# SCH_RPi5-GPIO-Breakout-Board-_AI-Capsule.net
KiCad netlist of a schematic drawn in EasyEDA
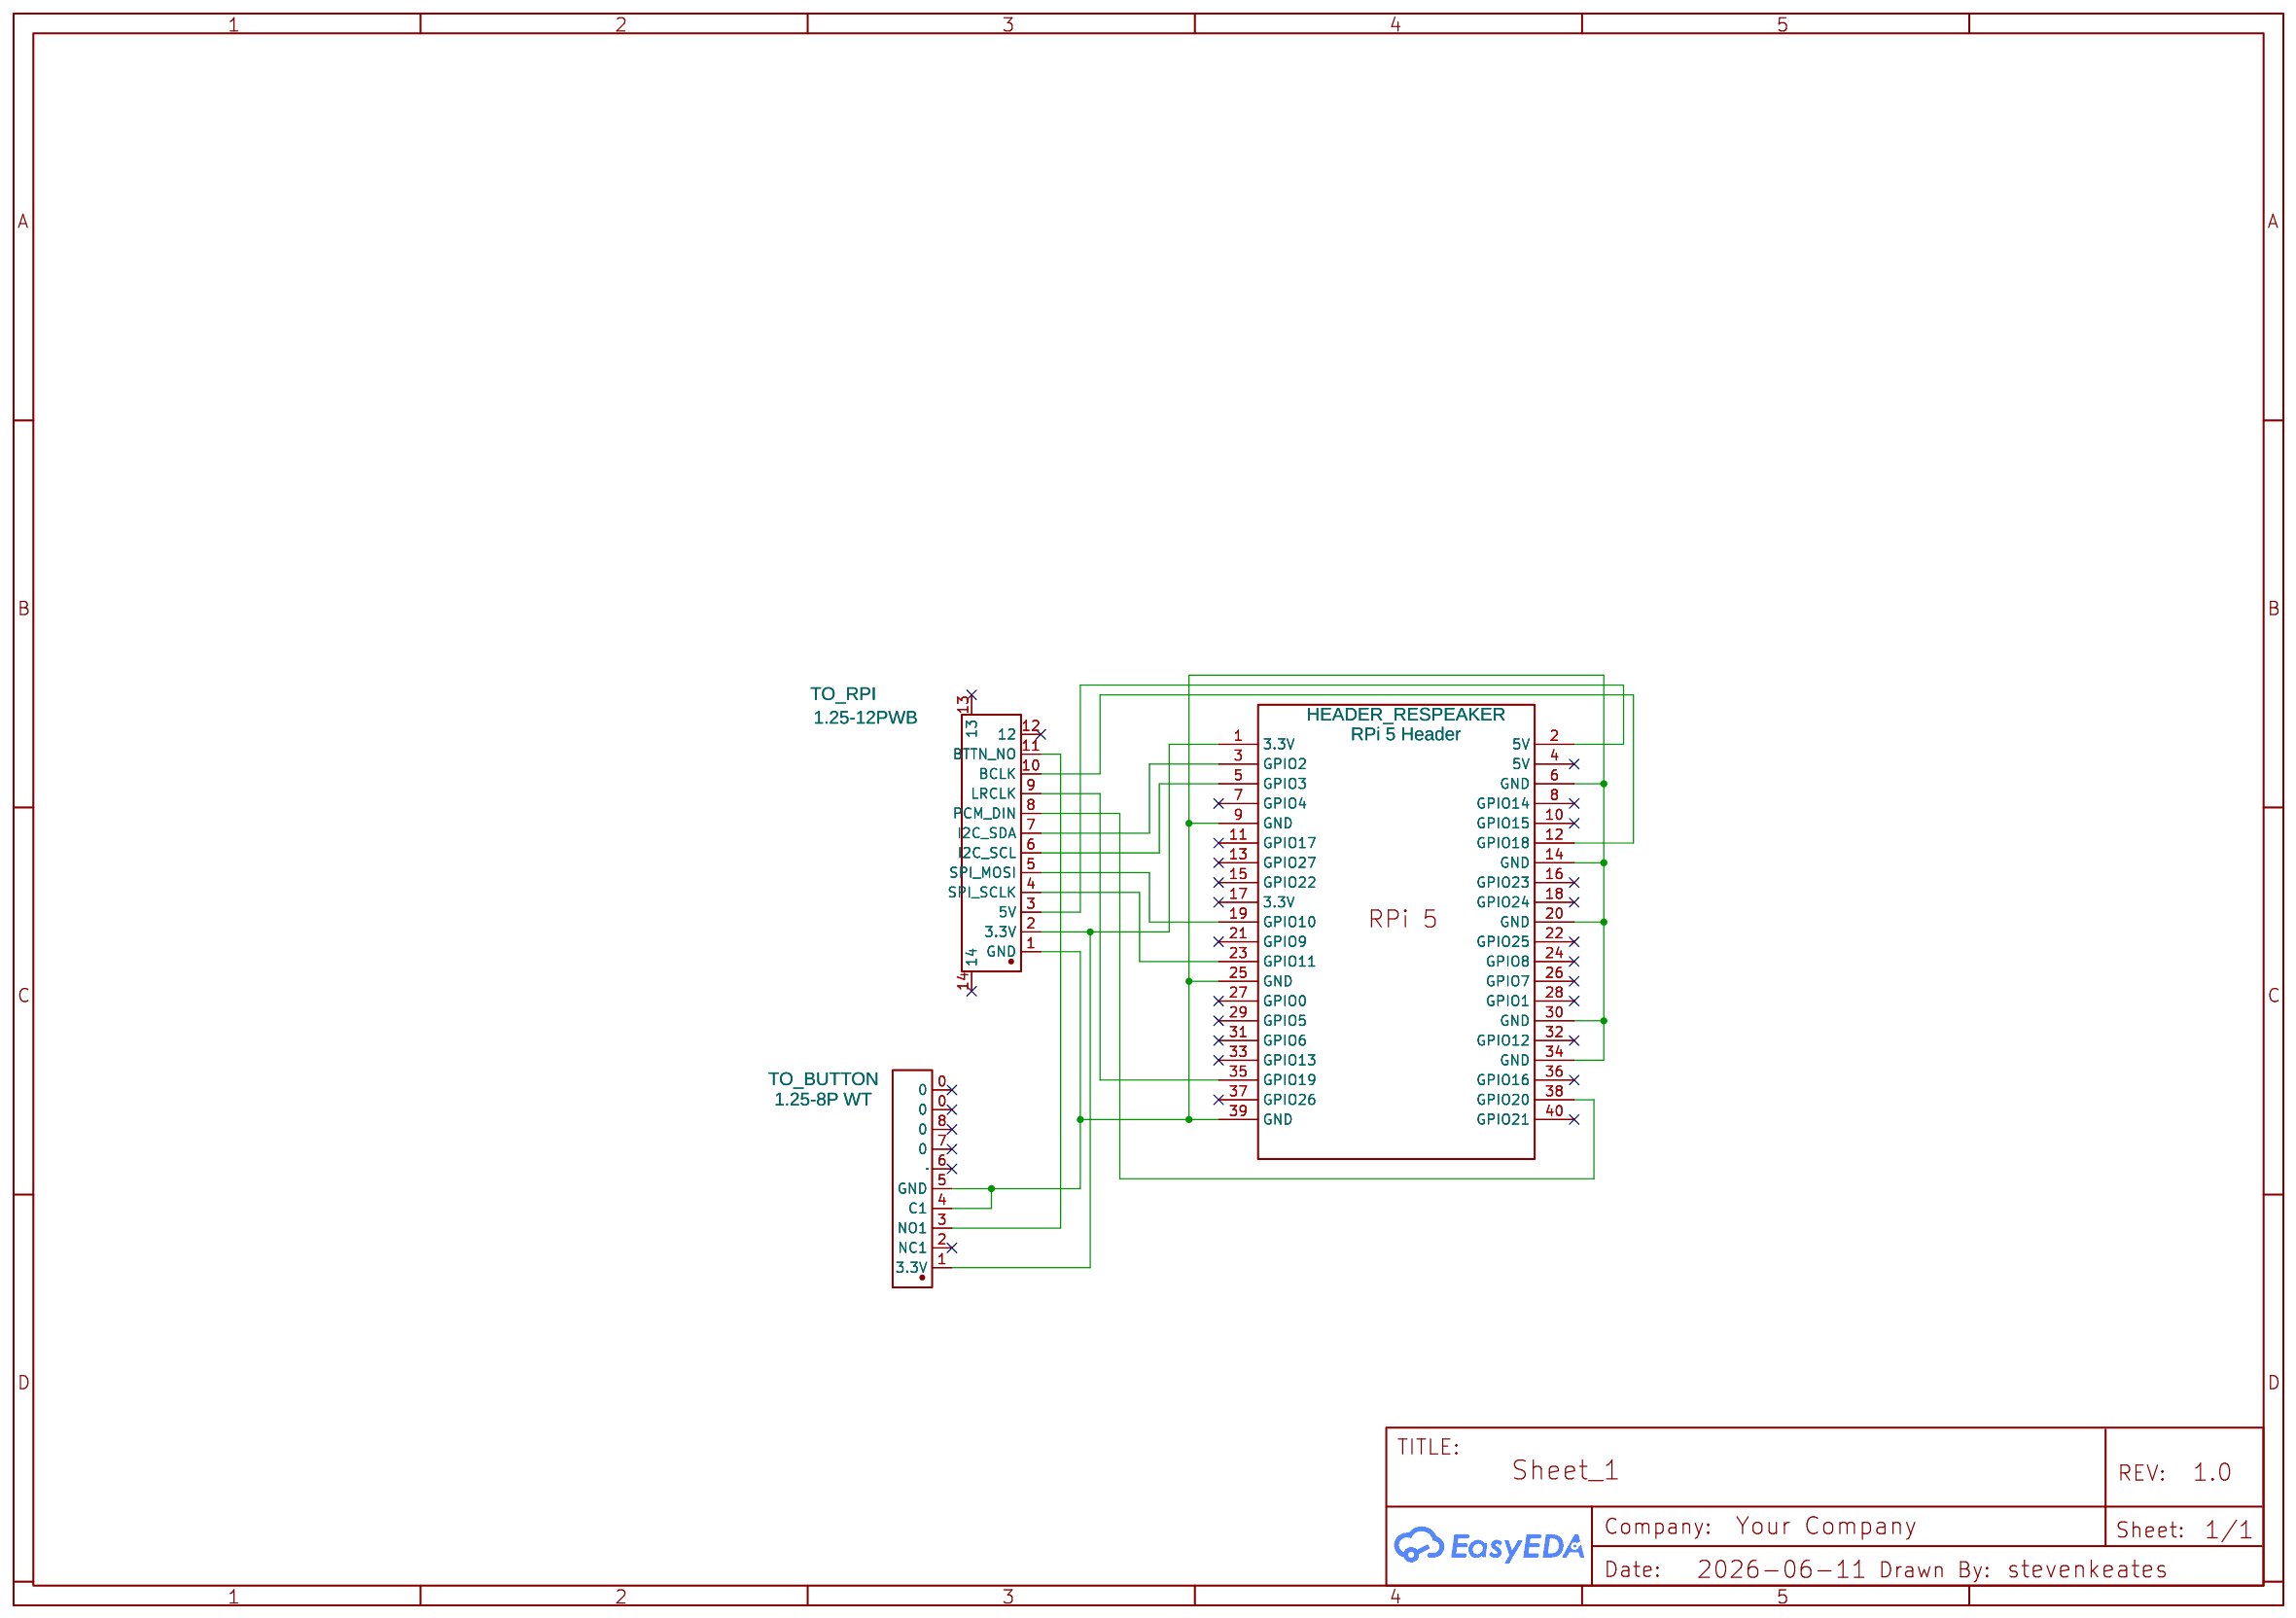
[diagram p0: SCH_Breakout Board (ReSpeaker)]
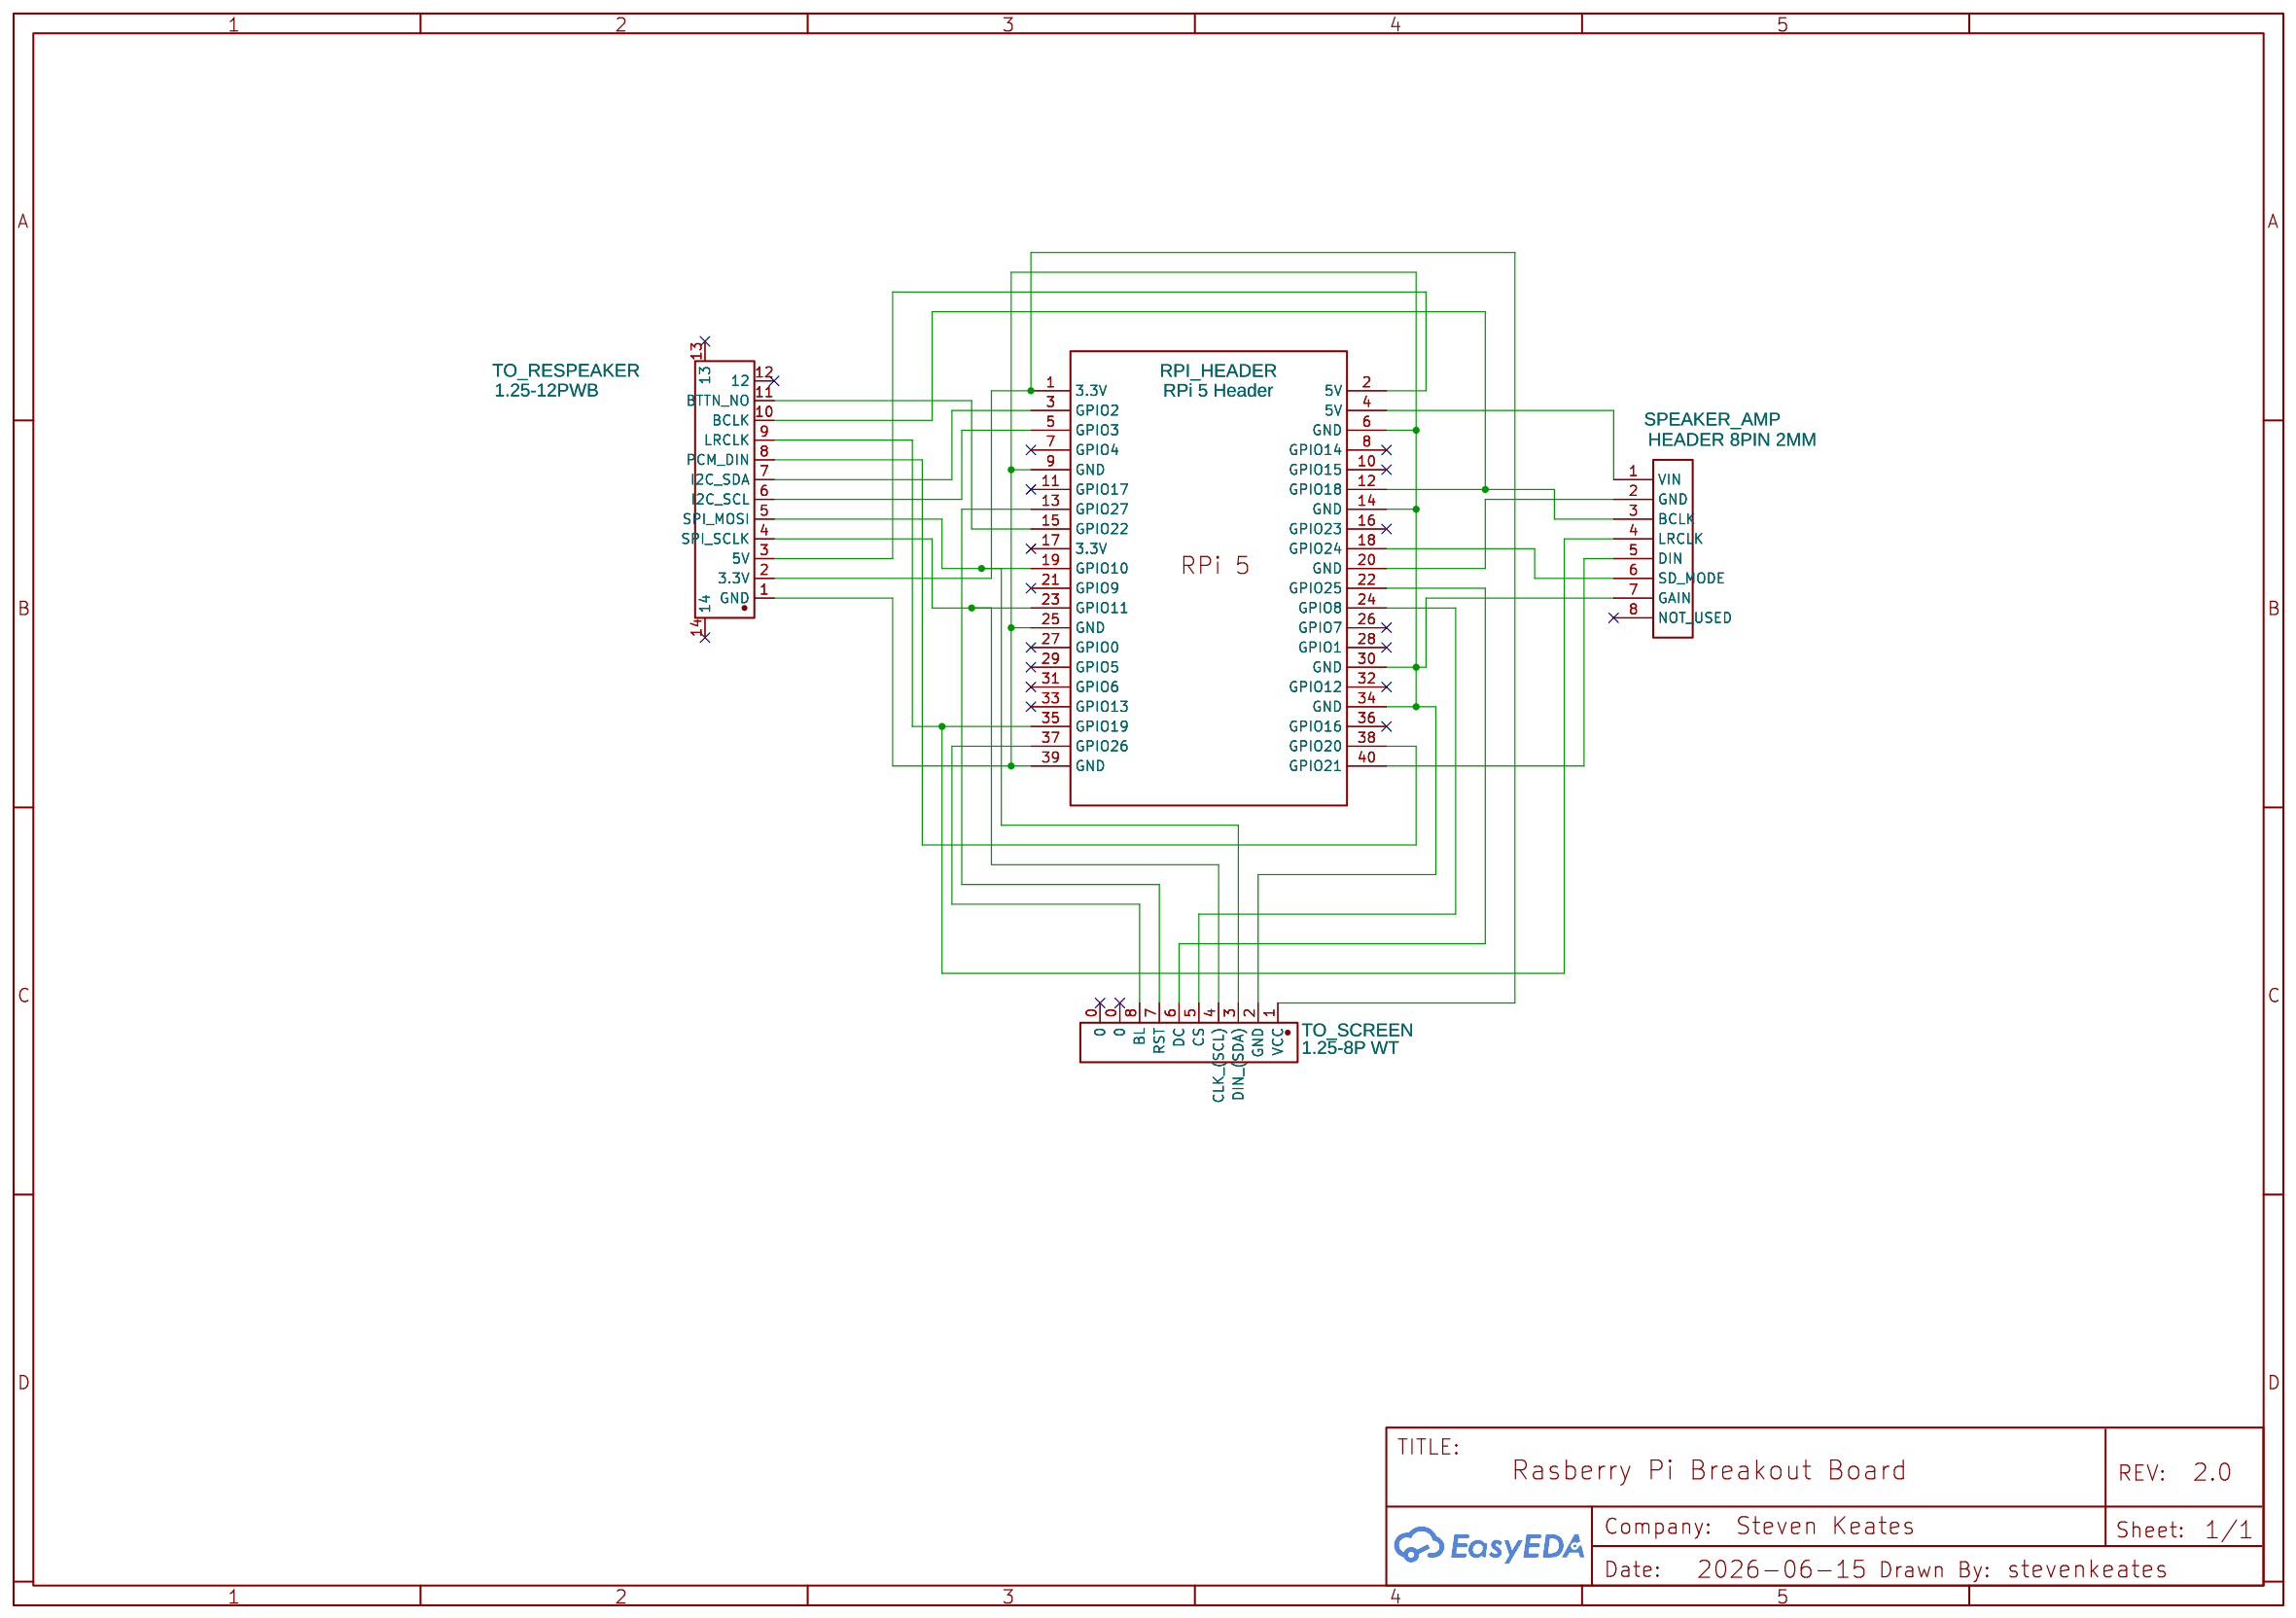
[diagram p1: SCH_Breakout Board (RPi 5)]

(export (version "E")
  (design (tool "Eeschema 10.0.6"))
  (components
    (comp (ref "HEADER_RESPEAKER")
      (value "RPi 5 Header")
      (fields (field (name "Manufacturer") "Raspberry Pi 5 4GB"))
      (libsource (lib "") (part "Raspberry Pi 5"))
    )
    (comp (ref "TO_BUTTON")
      (value "1.25-8P WT")
      (fields (field (name "Manufacturer") "SHOU HAN(首韩)"))
      (libsource (lib "") (part "1.25-8P WT"))
    )
    (comp (ref "TO_RPI")
      (value "1.25-12PWB")
      (fields (field (name "Manufacturer") "DEALON(德艺隆)"))
      (libsource (lib "") (part "1.25-12PWB"))
    )
    (comp (ref "RPI_HEADER")
      (value "RPi 5 Header")
      (fields (field (name "Manufacturer") "Raspberry Pi 5 4GB"))
      (libsource (lib "") (part "Raspberry Pi 5"))
    )
    (comp (ref "SPEAKER_AMP") (value "HEADER 8PIN 2MM") (libsource (lib "") (part "HEADER 8PIN 2MM")))
    (comp (ref "TO_RESPEAKER")
      (value "1.25-12PWB")
      (fields (field (name "Manufacturer") "DEALON(德艺隆)"))
      (libsource (lib "") (part "1.25-12PWB"))
    )
    (comp (ref "TO_SCREEN")
      (value "1.25-8P WT")
      (fields (field (name "Manufacturer") "SHOU HAN(首韩)"))
      (libsource (lib "") (part "1.25-8P WT"))
    )
  )
  (nets
    (net (code "1") (name "Net-(HEADER_RESPEAKER-GPIO2)") (class "Default")
      (node (ref "HEADER_RESPEAKER") (pin "3") (pinfunction "GPIO2_3") (pintype "unspecified"))
      (node (ref "TO_RPI") (pin "7") (pinfunction "I2C_SDA_7") (pintype "unspecified"))
    )
    (net (code "2") (name "Net-(HEADER_RESPEAKER-GPIO3)") (class "Default")
      (node (ref "HEADER_RESPEAKER") (pin "5") (pinfunction "GPIO3_5") (pintype "unspecified"))
      (node (ref "TO_RPI") (pin "6") (pinfunction "I2C_SCL_6") (pintype "unspecified"))
    )
    (net (code "3") (name "Net-(HEADER_RESPEAKER-GPIO10)") (class "Default")
      (node (ref "HEADER_RESPEAKER") (pin "19") (pinfunction "GPIO10_19") (pintype "unspecified"))
      (node (ref "TO_RPI") (pin "5") (pinfunction "SPI_MOSI_5") (pintype "unspecified"))
    )
    (net (code "4") (name "Net-(HEADER_RESPEAKER-GPIO11)") (class "Default")
      (node (ref "HEADER_RESPEAKER") (pin "23") (pinfunction "GPIO11_23") (pintype "unspecified"))
      (node (ref "TO_RPI") (pin "4") (pinfunction "SPI_SCLK_4") (pintype "unspecified"))
    )
    (net (code "5") (name "Net-(HEADER_RESPEAKER-GPIO18)") (class "Default")
      (node (ref "HEADER_RESPEAKER") (pin "12") (pinfunction "GPIO18_12") (pintype "unspecified"))
      (node (ref "TO_RPI") (pin "10") (pinfunction "BCLK_10") (pintype "unspecified"))
    )
    (net (code "6") (name "Net-(HEADER_RESPEAKER-GPIO19)") (class "Default")
      (node (ref "HEADER_RESPEAKER") (pin "35") (pinfunction "GPIO19_35") (pintype "unspecified"))
      (node (ref "TO_RPI") (pin "9") (pinfunction "LRCLK_9") (pintype "unspecified"))
    )
    (net (code "7") (name "Net-(HEADER_RESPEAKER-GPIO20)") (class "Default")
      (node (ref "HEADER_RESPEAKER") (pin "38") (pinfunction "GPIO20_38") (pintype "unspecified"))
      (node (ref "TO_RPI") (pin "8") (pinfunction "PCM_DIN_8") (pintype "unspecified"))
    )
    (net (code "8") (name "Net-(RPI_HEADER-GPIO2)") (class "Default")
      (node (ref "RPI_HEADER") (pin "3") (pinfunction "GPIO2_3") (pintype "unspecified"))
      (node (ref "TO_RESPEAKER") (pin "7") (pinfunction "I2C_SDA_7") (pintype "unspecified"))
    )
    (net (code "9") (name "Net-(RPI_HEADER-GPIO3)") (class "Default")
      (node (ref "RPI_HEADER") (pin "5") (pinfunction "GPIO3_5") (pintype "unspecified"))
      (node (ref "TO_RESPEAKER") (pin "6") (pinfunction "I2C_SCL_6") (pintype "unspecified"))
    )
    (net (code "10") (name "Net-(RPI_HEADER-GPIO8)") (class "Default")
      (node (ref "RPI_HEADER") (pin "24") (pinfunction "GPIO8_24") (pintype "unspecified"))
      (node (ref "TO_SCREEN") (pin "5") (pinfunction "CS_5") (pintype "unspecified"))
    )
    (net (code "11") (name "Net-(RPI_HEADER-GPIO10)") (class "Default")
      (node (ref "RPI_HEADER") (pin "19") (pinfunction "GPIO10_19") (pintype "unspecified"))
      (node (ref "TO_RESPEAKER") (pin "5") (pinfunction "SPI_MOSI_5") (pintype "unspecified"))
      (node (ref "TO_SCREEN") (pin "3") (pinfunction "DIN_(SDA)_3") (pintype "unspecified"))
    )
    (net (code "12") (name "Net-(RPI_HEADER-GPIO11)") (class "Default")
      (node (ref "RPI_HEADER") (pin "23") (pinfunction "GPIO11_23") (pintype "unspecified"))
      (node (ref "TO_RESPEAKER") (pin "4") (pinfunction "SPI_SCLK_4") (pintype "unspecified"))
      (node (ref "TO_SCREEN") (pin "4") (pinfunction "CLK_(SCL)_4") (pintype "unspecified"))
    )
    (net (code "13") (name "Net-(RPI_HEADER-GPIO18)") (class "Default")
      (node (ref "RPI_HEADER") (pin "12") (pinfunction "GPIO18_12") (pintype "unspecified"))
      (node (ref "SPEAKER_AMP") (pin "3") (pinfunction "BCLK_3") (pintype "unspecified"))
      (node (ref "TO_RESPEAKER") (pin "10") (pinfunction "BCLK_10") (pintype "unspecified"))
    )
    (net (code "14") (name "Net-(RPI_HEADER-GPIO19)") (class "Default")
      (node (ref "RPI_HEADER") (pin "35") (pinfunction "GPIO19_35") (pintype "unspecified"))
      (node (ref "SPEAKER_AMP") (pin "4") (pinfunction "LRCLK_4") (pintype "unspecified"))
      (node (ref "TO_RESPEAKER") (pin "9") (pinfunction "LRCLK_9") (pintype "unspecified"))
    )
    (net (code "15") (name "Net-(RPI_HEADER-GPIO20)") (class "Default")
      (node (ref "RPI_HEADER") (pin "38") (pinfunction "GPIO20_38") (pintype "unspecified"))
      (node (ref "TO_RESPEAKER") (pin "8") (pinfunction "PCM_DIN_8") (pintype "unspecified"))
    )
    (net (code "16") (name "Net-(RPI_HEADER-GPIO21)") (class "Default")
      (node (ref "RPI_HEADER") (pin "40") (pinfunction "GPIO21_40") (pintype "unspecified"))
      (node (ref "SPEAKER_AMP") (pin "5") (pinfunction "DIN_5") (pintype "unspecified"))
    )
    (net (code "17") (name "Net-(RPI_HEADER-GPIO22)") (class "Default")
      (node (ref "RPI_HEADER") (pin "15") (pinfunction "GPIO22_15") (pintype "unspecified"))
      (node (ref "TO_RESPEAKER") (pin "11") (pinfunction "BTTN_NO_11") (pintype "unspecified"))
    )
    (net (code "18") (name "Net-(RPI_HEADER-GPIO24)") (class "Default")
      (node (ref "RPI_HEADER") (pin "18") (pinfunction "GPIO24_18") (pintype "unspecified"))
      (node (ref "SPEAKER_AMP") (pin "6") (pinfunction "SD_MODE_6") (pintype "unspecified"))
    )
    (net (code "19") (name "Net-(RPI_HEADER-GPIO25)") (class "Default")
      (node (ref "RPI_HEADER") (pin "22") (pinfunction "GPIO25_22") (pintype "unspecified"))
      (node (ref "TO_SCREEN") (pin "6") (pinfunction "DC_6") (pintype "unspecified"))
    )
    (net (code "20") (name "Net-(RPI_HEADER-GPIO26)") (class "Default")
      (node (ref "RPI_HEADER") (pin "37") (pinfunction "GPIO26_37") (pintype "unspecified"))
      (node (ref "TO_SCREEN") (pin "8") (pinfunction "BL_8") (pintype "unspecified"))
    )
    (net (code "21") (name "Net-(RPI_HEADER-GPIO27)") (class "Default")
      (node (ref "RPI_HEADER") (pin "13") (pinfunction "GPIO27_13") (pintype "unspecified"))
      (node (ref "TO_SCREEN") (pin "7") (pinfunction "RST_7") (pintype "unspecified"))
    )
    (net (code "22") (name "Net-(SPEAKER_AMP-GAIN)") (class "Default")
      (node (ref "RPI_HEADER") (pin "14") (pinfunction "GND_14") (pintype "unspecified"))
      (node (ref "RPI_HEADER") (pin "25") (pinfunction "GND_25") (pintype "unspecified"))
      (node (ref "RPI_HEADER") (pin "30") (pinfunction "GND_30") (pintype "unspecified"))
      (node (ref "RPI_HEADER") (pin "34") (pinfunction "GND_34") (pintype "unspecified"))
      (node (ref "RPI_HEADER") (pin "39") (pinfunction "GND_39") (pintype "unspecified"))
      (node (ref "RPI_HEADER") (pin "6") (pinfunction "GND_6") (pintype "unspecified"))
      (node (ref "RPI_HEADER") (pin "9") (pinfunction "GND_9") (pintype "unspecified"))
      (node (ref "SPEAKER_AMP") (pin "7") (pinfunction "GAIN_7") (pintype "unspecified"))
      (node (ref "TO_RESPEAKER") (pin "1") (pinfunction "GND_1") (pintype "unspecified"))
      (node (ref "TO_SCREEN") (pin "2") (pinfunction "GND_2") (pintype "unspecified"))
    )
    (net (code "23") (name "Net-(SPEAKER_AMP-GND)") (class "Default")
      (node (ref "RPI_HEADER") (pin "20") (pinfunction "GND_20") (pintype "unspecified"))
      (node (ref "SPEAKER_AMP") (pin "2") (pinfunction "GND_2") (pintype "unspecified"))
    )
    (net (code "24") (name "Net-(SPEAKER_AMP-VIN)") (class "Default")
      (node (ref "RPI_HEADER") (pin "4") (pinfunction "5V_4") (pintype "unspecified"))
      (node (ref "SPEAKER_AMP") (pin "1") (pinfunction "VIN_1") (pintype "unspecified"))
    )
    (net (code "25") (name "Net-(TO_BUTTON-3.3V)") (class "Default")
      (node (ref "HEADER_RESPEAKER") (pin "1") (pinfunction "3.3V_1") (pintype "unspecified"))
      (node (ref "TO_BUTTON") (pin "1") (pinfunction "3.3V_1") (pintype "unspecified"))
      (node (ref "TO_RPI") (pin "2") (pinfunction "3.3V_2") (pintype "unspecified"))
    )
    (net (code "26") (name "Net-(TO_BUTTON-C1)") (class "Default")
      (node (ref "HEADER_RESPEAKER") (pin "14") (pinfunction "GND_14") (pintype "unspecified"))
      (node (ref "HEADER_RESPEAKER") (pin "20") (pinfunction "GND_20") (pintype "unspecified"))
      (node (ref "HEADER_RESPEAKER") (pin "25") (pinfunction "GND_25") (pintype "unspecified"))
      (node (ref "HEADER_RESPEAKER") (pin "30") (pinfunction "GND_30") (pintype "unspecified"))
      (node (ref "HEADER_RESPEAKER") (pin "34") (pinfunction "GND_34") (pintype "unspecified"))
      (node (ref "HEADER_RESPEAKER") (pin "39") (pinfunction "GND_39") (pintype "unspecified"))
      (node (ref "HEADER_RESPEAKER") (pin "6") (pinfunction "GND_6") (pintype "unspecified"))
      (node (ref "HEADER_RESPEAKER") (pin "9") (pinfunction "GND_9") (pintype "unspecified"))
      (node (ref "TO_BUTTON") (pin "4") (pinfunction "C1_4") (pintype "unspecified"))
      (node (ref "TO_BUTTON") (pin "5") (pinfunction "GND_5") (pintype "unspecified"))
      (node (ref "TO_RPI") (pin "1") (pinfunction "GND_1") (pintype "unspecified"))
    )
    (net (code "27") (name "Net-(TO_BUTTON-NO1)") (class "Default")
      (node (ref "TO_BUTTON") (pin "3") (pinfunction "NO1_3") (pintype "unspecified"))
      (node (ref "TO_RPI") (pin "11") (pinfunction "BTTN_NO_11") (pintype "unspecified"))
    )
    (net (code "28") (name "Net-(TO_RESPEAKER-3.3V)") (class "Default")
      (node (ref "RPI_HEADER") (pin "1") (pinfunction "3.3V_1") (pintype "unspecified"))
      (node (ref "TO_RESPEAKER") (pin "2") (pinfunction "3.3V_2") (pintype "unspecified"))
      (node (ref "TO_SCREEN") (pin "1") (pinfunction "VCC_1") (pintype "unspecified"))
    )
    (net (code "29") (name "Net-(TO_RESPEAKER-5V)") (class "Default")
      (node (ref "RPI_HEADER") (pin "2") (pinfunction "5V_2") (pintype "unspecified"))
      (node (ref "TO_RESPEAKER") (pin "3") (pinfunction "5V_3") (pintype "unspecified"))
    )
    (net (code "30") (name "Net-(TO_RPI-5V)") (class "Default")
      (node (ref "HEADER_RESPEAKER") (pin "2") (pinfunction "5V_2") (pintype "unspecified"))
      (node (ref "TO_RPI") (pin "3") (pinfunction "5V_3") (pintype "unspecified"))
    )
    (net (code "31") (name "unconnected-(HEADER_RESPEAKER-3.3V-Pad17)") (class "Default")
      (node (ref "HEADER_RESPEAKER") (pin "17") (pinfunction "3.3V_17") (pintype "unspecified+no_connect"))
    )
    (net (code "32") (name "unconnected-(HEADER_RESPEAKER-5V-Pad4)") (class "Default")
      (node (ref "HEADER_RESPEAKER") (pin "4") (pinfunction "5V_4") (pintype "unspecified+no_connect"))
    )
    (net (code "33") (name "unconnected-(HEADER_RESPEAKER-GPIO0-Pad27)") (class "Default")
      (node (ref "HEADER_RESPEAKER") (pin "27") (pinfunction "GPIO0_27") (pintype "unspecified+no_connect"))
    )
    (net (code "34") (name "unconnected-(HEADER_RESPEAKER-GPIO1-Pad28)") (class "Default")
      (node (ref "HEADER_RESPEAKER") (pin "28") (pinfunction "GPIO1_28") (pintype "unspecified+no_connect"))
    )
    (net (code "35") (name "unconnected-(HEADER_RESPEAKER-GPIO4-Pad7)") (class "Default")
      (node (ref "HEADER_RESPEAKER") (pin "7") (pinfunction "GPIO4_7") (pintype "unspecified+no_connect"))
    )
    (net (code "36") (name "unconnected-(HEADER_RESPEAKER-GPIO5-Pad29)") (class "Default")
      (node (ref "HEADER_RESPEAKER") (pin "29") (pinfunction "GPIO5_29") (pintype "unspecified+no_connect"))
    )
    (net (code "37") (name "unconnected-(HEADER_RESPEAKER-GPIO6-Pad31)") (class "Default")
      (node (ref "HEADER_RESPEAKER") (pin "31") (pinfunction "GPIO6_31") (pintype "unspecified+no_connect"))
    )
    (net (code "38") (name "unconnected-(HEADER_RESPEAKER-GPIO7-Pad26)") (class "Default")
      (node (ref "HEADER_RESPEAKER") (pin "26") (pinfunction "GPIO7_26") (pintype "unspecified+no_connect"))
    )
    (net (code "39") (name "unconnected-(HEADER_RESPEAKER-GPIO8-Pad24)") (class "Default")
      (node (ref "HEADER_RESPEAKER") (pin "24") (pinfunction "GPIO8_24") (pintype "unspecified+no_connect"))
    )
    (net (code "40") (name "unconnected-(HEADER_RESPEAKER-GPIO9-Pad21)") (class "Default")
      (node (ref "HEADER_RESPEAKER") (pin "21") (pinfunction "GPIO9_21") (pintype "unspecified+no_connect"))
    )
    (net (code "41") (name "unconnected-(HEADER_RESPEAKER-GPIO12-Pad32)") (class "Default")
      (node (ref "HEADER_RESPEAKER") (pin "32") (pinfunction "GPIO12_32") (pintype "unspecified+no_connect"))
    )
    (net (code "42") (name "unconnected-(HEADER_RESPEAKER-GPIO13-Pad33)") (class "Default")
      (node (ref "HEADER_RESPEAKER") (pin "33") (pinfunction "GPIO13_33") (pintype "unspecified+no_connect"))
    )
    (net (code "43") (name "unconnected-(HEADER_RESPEAKER-GPIO14-Pad8)") (class "Default")
      (node (ref "HEADER_RESPEAKER") (pin "8") (pinfunction "GPIO14_8") (pintype "unspecified+no_connect"))
    )
    (net (code "44") (name "unconnected-(HEADER_RESPEAKER-GPIO15-Pad10)") (class "Default")
      (node (ref "HEADER_RESPEAKER") (pin "10") (pinfunction "GPIO15_10") (pintype "unspecified+no_connect"))
    )
    (net (code "45") (name "unconnected-(HEADER_RESPEAKER-GPIO16-Pad36)") (class "Default")
      (node (ref "HEADER_RESPEAKER") (pin "36") (pinfunction "GPIO16_36") (pintype "unspecified+no_connect"))
    )
    (net (code "46") (name "unconnected-(HEADER_RESPEAKER-GPIO17-Pad11)") (class "Default")
      (node (ref "HEADER_RESPEAKER") (pin "11") (pinfunction "GPIO17_11") (pintype "unspecified+no_connect"))
    )
    (net (code "47") (name "unconnected-(HEADER_RESPEAKER-GPIO21-Pad40)") (class "Default")
      (node (ref "HEADER_RESPEAKER") (pin "40") (pinfunction "GPIO21_40") (pintype "unspecified+no_connect"))
    )
    (net (code "48") (name "unconnected-(HEADER_RESPEAKER-GPIO22-Pad15)") (class "Default")
      (node (ref "HEADER_RESPEAKER") (pin "15") (pinfunction "GPIO22_15") (pintype "unspecified+no_connect"))
    )
    (net (code "49") (name "unconnected-(HEADER_RESPEAKER-GPIO23-Pad16)") (class "Default")
      (node (ref "HEADER_RESPEAKER") (pin "16") (pinfunction "GPIO23_16") (pintype "unspecified+no_connect"))
    )
    (net (code "50") (name "unconnected-(HEADER_RESPEAKER-GPIO24-Pad18)") (class "Default")
      (node (ref "HEADER_RESPEAKER") (pin "18") (pinfunction "GPIO24_18") (pintype "unspecified+no_connect"))
    )
    (net (code "51") (name "unconnected-(HEADER_RESPEAKER-GPIO25-Pad22)") (class "Default")
      (node (ref "HEADER_RESPEAKER") (pin "22") (pinfunction "GPIO25_22") (pintype "unspecified+no_connect"))
    )
    (net (code "52") (name "unconnected-(HEADER_RESPEAKER-GPIO26-Pad37)") (class "Default")
      (node (ref "HEADER_RESPEAKER") (pin "37") (pinfunction "GPIO26_37") (pintype "unspecified+no_connect"))
    )
    (net (code "53") (name "unconnected-(HEADER_RESPEAKER-GPIO27-Pad13)") (class "Default")
      (node (ref "HEADER_RESPEAKER") (pin "13") (pinfunction "GPIO27_13") (pintype "unspecified+no_connect"))
    )
    (net (code "54") (name "unconnected-(RPI_HEADER-3.3V-Pad17)") (class "Default")
      (node (ref "RPI_HEADER") (pin "17") (pinfunction "3.3V_17") (pintype "unspecified+no_connect"))
    )
    (net (code "55") (name "unconnected-(RPI_HEADER-GPIO0-Pad27)") (class "Default")
      (node (ref "RPI_HEADER") (pin "27") (pinfunction "GPIO0_27") (pintype "unspecified+no_connect"))
    )
    (net (code "56") (name "unconnected-(RPI_HEADER-GPIO1-Pad28)") (class "Default")
      (node (ref "RPI_HEADER") (pin "28") (pinfunction "GPIO1_28") (pintype "unspecified+no_connect"))
    )
    (net (code "57") (name "unconnected-(RPI_HEADER-GPIO4-Pad7)") (class "Default")
      (node (ref "RPI_HEADER") (pin "7") (pinfunction "GPIO4_7") (pintype "unspecified+no_connect"))
    )
    (net (code "58") (name "unconnected-(RPI_HEADER-GPIO5-Pad29)") (class "Default")
      (node (ref "RPI_HEADER") (pin "29") (pinfunction "GPIO5_29") (pintype "unspecified+no_connect"))
    )
    (net (code "59") (name "unconnected-(RPI_HEADER-GPIO6-Pad31)") (class "Default")
      (node (ref "RPI_HEADER") (pin "31") (pinfunction "GPIO6_31") (pintype "unspecified+no_connect"))
    )
    (net (code "60") (name "unconnected-(RPI_HEADER-GPIO7-Pad26)") (class "Default")
      (node (ref "RPI_HEADER") (pin "26") (pinfunction "GPIO7_26") (pintype "unspecified+no_connect"))
    )
    (net (code "61") (name "unconnected-(RPI_HEADER-GPIO9-Pad21)") (class "Default")
      (node (ref "RPI_HEADER") (pin "21") (pinfunction "GPIO9_21") (pintype "unspecified+no_connect"))
    )
    (net (code "62") (name "unconnected-(RPI_HEADER-GPIO12-Pad32)") (class "Default")
      (node (ref "RPI_HEADER") (pin "32") (pinfunction "GPIO12_32") (pintype "unspecified+no_connect"))
    )
    (net (code "63") (name "unconnected-(RPI_HEADER-GPIO13-Pad33)") (class "Default")
      (node (ref "RPI_HEADER") (pin "33") (pinfunction "GPIO13_33") (pintype "unspecified+no_connect"))
    )
    (net (code "64") (name "unconnected-(RPI_HEADER-GPIO14-Pad8)") (class "Default")
      (node (ref "RPI_HEADER") (pin "8") (pinfunction "GPIO14_8") (pintype "unspecified+no_connect"))
    )
    (net (code "65") (name "unconnected-(RPI_HEADER-GPIO15-Pad10)") (class "Default")
      (node (ref "RPI_HEADER") (pin "10") (pinfunction "GPIO15_10") (pintype "unspecified+no_connect"))
    )
    (net (code "66") (name "unconnected-(RPI_HEADER-GPIO16-Pad36)") (class "Default")
      (node (ref "RPI_HEADER") (pin "36") (pinfunction "GPIO16_36") (pintype "unspecified+no_connect"))
    )
    (net (code "67") (name "unconnected-(RPI_HEADER-GPIO17-Pad11)") (class "Default")
      (node (ref "RPI_HEADER") (pin "11") (pinfunction "GPIO17_11") (pintype "unspecified+no_connect"))
    )
    (net (code "68") (name "unconnected-(RPI_HEADER-GPIO23-Pad16)") (class "Default")
      (node (ref "RPI_HEADER") (pin "16") (pinfunction "GPIO23_16") (pintype "unspecified+no_connect"))
    )
    (net (code "69") (name "unconnected-(SPEAKER_AMP-NOT_USED-Pad8)") (class "Default")
      (node (ref "SPEAKER_AMP") (pin "8") (pinfunction "NOT_USED_8") (pintype "unspecified+no_connect"))
    )
    (net (code "70") (name "unconnected-(TO_BUTTON-0-Pad7)") (class "Default")
      (node (ref "TO_BUTTON") (pin "7") (pinfunction "0_7") (pintype "unspecified+no_connect"))
    )
    (net (code "71") (name "unconnected-(TO_BUTTON-0-Pad8)") (class "Default")
      (node (ref "TO_BUTTON") (pin "8") (pinfunction "0_8") (pintype "unspecified+no_connect"))
    )
    (net (code "72") (name "unconnected-(TO_BUTTON-DC-Pad6)") (class "Default")
      (node (ref "TO_BUTTON") (pin "6") (pinfunction "DC_6") (pintype "unspecified+no_connect"))
    )
    (net (code "73") (name "unconnected-(TO_BUTTON-NC1-Pad2)") (class "Default")
      (node (ref "TO_BUTTON") (pin "2") (pinfunction "NC1_2") (pintype "unspecified+no_connect"))
    )
    (net (code "74") (name "unconnected-(TO_BUTTON-Pad0)") (class "Default")
      (node (ref "TO_BUTTON") (pin "0") (pinfunction "0_0") (pintype "unspecified+no_connect"))
    )
    (net (code "75") (name "unconnected-(TO_BUTTON-Pad0)_1") (class "Default")
      (node (ref "TO_BUTTON") (pin "0") (pinfunction "0_0") (pintype "unspecified+no_connect"))
    )
    (net (code "76") (name "unconnected-(TO_RESPEAKER-Pad12)") (class "Default")
      (node (ref "TO_RESPEAKER") (pin "12") (pinfunction "12_12") (pintype "unspecified+no_connect"))
    )
    (net (code "77") (name "unconnected-(TO_RESPEAKER-Pad13)") (class "Default")
      (node (ref "TO_RESPEAKER") (pin "13") (pinfunction "13_13") (pintype "unspecified+no_connect"))
    )
    (net (code "78") (name "unconnected-(TO_RESPEAKER-Pad14)") (class "Default")
      (node (ref "TO_RESPEAKER") (pin "14") (pinfunction "14_14") (pintype "unspecified+no_connect"))
    )
    (net (code "79") (name "unconnected-(TO_RPI-Pad12)") (class "Default")
      (node (ref "TO_RPI") (pin "12") (pinfunction "12_12") (pintype "unspecified+no_connect"))
    )
    (net (code "80") (name "unconnected-(TO_RPI-Pad13)") (class "Default")
      (node (ref "TO_RPI") (pin "13") (pinfunction "13_13") (pintype "unspecified+no_connect"))
    )
    (net (code "81") (name "unconnected-(TO_RPI-Pad14)") (class "Default")
      (node (ref "TO_RPI") (pin "14") (pinfunction "14_14") (pintype "unspecified+no_connect"))
    )
    (net (code "82") (name "unconnected-(TO_SCREEN-Pad0)") (class "Default")
      (node (ref "TO_SCREEN") (pin "0") (pinfunction "0_0") (pintype "unspecified+no_connect"))
    )
    (net (code "83") (name "unconnected-(TO_SCREEN-Pad0)_1") (class "Default")
      (node (ref "TO_SCREEN") (pin "0") (pinfunction "0_0") (pintype "unspecified+no_connect"))
    )
  )
)
